# PCB-SSB-2x1.net
KiCad netlist of a schematic drawn in EAGLE
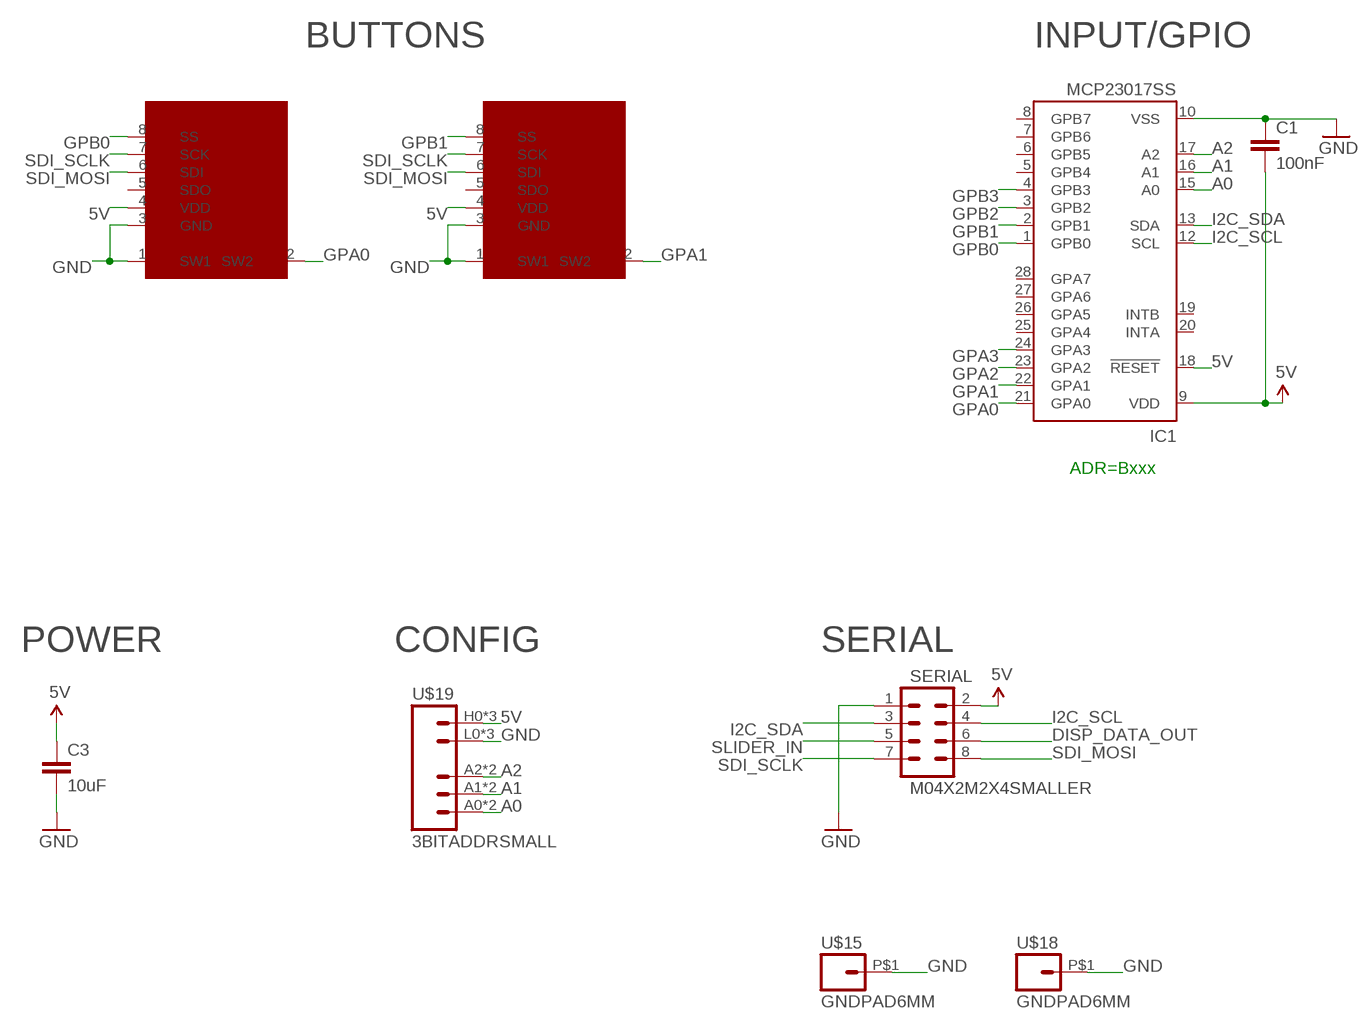
[diagram p0: schematic, sheet 1]

(export (version "E")
  (design (tool "Eeschema 10.0.6"))
  (components
    (comp (ref "C1")
      (value "100nF")
      (footprint "eagle-import:0603-CAP")
      (libsource (lib "eagle-import") (part "CAP0603-CAP"))
    )
    (comp (ref "C3")
      (value "10uF")
      (footprint "eagle-import:0805")
      (libsource (lib "eagle-import") (part "CAP0805"))
    )
    (comp (ref "IC1")
      (value "MCP23017SS")
      (footprint "eagle-import:SSOP28")
      (fields
        (field (name "MF") "MICROCHIP")
        (field (name "MPN") "MCP23017-E/SS")
        (field (name "MPN_1") "MCP23017-E/SS")
        (field (name "OC_FARNELL") "1467674")
        (field (name "OC_NEWARK") "31K2960")
      )
      (libsource (lib "eagle-import") (part "MCP23017SS"))
    )
    (comp (ref "SERIAL")
      (value "M04X2M2X4SMALLER")
      (footprint "eagle-import:M2X4SMALLER")
      (libsource (lib "eagle-import") (part "M04X2M2X4SMALLER"))
    )
    (comp (ref "SSW1")
      (value "SMART_SWITCHSMART_SWITCH_8PIN")
      (footprint "eagle-import:SMART_SWITCH")
      (libsource (lib "eagle-import") (part "SMART_SWITCHSMART_SWITCH_8PIN"))
    )
    (comp (ref "SSW2")
      (value "SMART_SWITCHSMART_SWITCH_8PIN")
      (footprint "eagle-import:SMART_SWITCH")
      (libsource (lib "eagle-import") (part "SMART_SWITCHSMART_SWITCH_8PIN"))
    )
    (comp (ref "U$15")
      (value "GNDPAD6MM")
      (footprint "eagle-import:3.2MMPAD6MM")
      (libsource (lib "eagle-import") (part "GNDPAD6MM"))
    )
    (comp (ref "U$18")
      (value "GNDPAD6MM")
      (footprint "eagle-import:3.2MMPAD6MM")
      (libsource (lib "eagle-import") (part "GNDPAD6MM"))
    )
    (comp (ref "U$19")
      (value "3BITADDRSMALL")
      (footprint "eagle-import:3BITADDR_SMALL")
      (libsource (lib "eagle-import") (part "3BITADDRSMALL"))
    )
  )
  (nets
    (net (code "1") (name "/A0") (class "Default")
      (node (ref "IC1") (pin "15") (pinfunction "A0_15") (pintype "input"))
      (node (ref "U$19") (pin "A0") (pinfunction "A0_A0") (pintype "passive"))
      (node (ref "U$19") (pin "AS0") (pinfunction "A0_AS0") (pintype "passive"))
    )
    (net (code "2") (name "/A1") (class "Default")
      (node (ref "IC1") (pin "16") (pinfunction "A1_16") (pintype "input"))
      (node (ref "U$19") (pin "A1") (pinfunction "A1_A1") (pintype "passive"))
      (node (ref "U$19") (pin "AS1") (pinfunction "A1_AS1") (pintype "passive"))
    )
    (net (code "3") (name "/A2") (class "Default")
      (node (ref "IC1") (pin "17") (pinfunction "A2_17") (pintype "input"))
      (node (ref "U$19") (pin "A2") (pinfunction "A2_A2") (pintype "passive"))
      (node (ref "U$19") (pin "AS2") (pinfunction "A2_AS2") (pintype "passive"))
    )
    (net (code "4") (name "/DISP_DATA_OUT") (class "Default")
      (node (ref "SERIAL") (pin "6") (pinfunction "6_6") (pintype "passive"))
    )
    (net (code "5") (name "/GPA0") (class "Default")
      (node (ref "IC1") (pin "21") (pinfunction "GPA0_21") (pintype "bidirectional"))
      (node (ref "SSW1") (pin "2") (pinfunction "SW2_2") (pintype "bidirectional"))
    )
    (net (code "6") (name "/GPA1") (class "Default")
      (node (ref "IC1") (pin "22") (pinfunction "GPA1_22") (pintype "bidirectional"))
      (node (ref "SSW2") (pin "2") (pinfunction "SW2_2") (pintype "bidirectional"))
    )
    (net (code "7") (name "/GPA2") (class "Default")
      (node (ref "IC1") (pin "23") (pinfunction "GPA2_23") (pintype "bidirectional"))
    )
    (net (code "8") (name "/GPA3") (class "Default")
      (node (ref "IC1") (pin "24") (pinfunction "GPA3_24") (pintype "bidirectional"))
    )
    (net (code "9") (name "/GPB0") (class "Default")
      (node (ref "IC1") (pin "1") (pinfunction "GPB0_1") (pintype "bidirectional"))
      (node (ref "SSW1") (pin "8") (pinfunction "SS_8") (pintype "bidirectional"))
    )
    (net (code "10") (name "/GPB1") (class "Default")
      (node (ref "IC1") (pin "2") (pinfunction "GPB1_2") (pintype "bidirectional"))
      (node (ref "SSW2") (pin "8") (pinfunction "SS_8") (pintype "bidirectional"))
    )
    (net (code "11") (name "/GPB2") (class "Default")
      (node (ref "IC1") (pin "3") (pinfunction "GPB2_3") (pintype "bidirectional"))
    )
    (net (code "12") (name "/GPB3") (class "Default")
      (node (ref "IC1") (pin "4") (pinfunction "GPB3_4") (pintype "bidirectional"))
    )
    (net (code "13") (name "/I2C_SCL") (class "Default")
      (node (ref "IC1") (pin "12") (pinfunction "SCL_12") (pintype "input"))
      (node (ref "SERIAL") (pin "4") (pinfunction "4_4") (pintype "passive"))
    )
    (net (code "14") (name "/I2C_SDA") (class "Default")
      (node (ref "IC1") (pin "13") (pinfunction "SDA_13") (pintype "bidirectional"))
      (node (ref "SERIAL") (pin "3") (pinfunction "3_3") (pintype "passive"))
    )
    (net (code "15") (name "/SDI_MOSI") (class "Default")
      (node (ref "SERIAL") (pin "8") (pinfunction "8_8") (pintype "passive"))
      (node (ref "SSW1") (pin "6") (pinfunction "SDI_6") (pintype "bidirectional"))
      (node (ref "SSW2") (pin "6") (pinfunction "SDI_6") (pintype "bidirectional"))
    )
    (net (code "16") (name "/SDI_SCLK") (class "Default")
      (node (ref "SERIAL") (pin "7") (pinfunction "7_7") (pintype "passive"))
      (node (ref "SSW1") (pin "7") (pinfunction "SCK_7") (pintype "bidirectional"))
      (node (ref "SSW2") (pin "7") (pinfunction "SCK_7") (pintype "bidirectional"))
    )
    (net (code "17") (name "/SLIDER_IN") (class "Default")
      (node (ref "SERIAL") (pin "5") (pinfunction "5_5") (pintype "passive"))
    )
    (net (code "18") (name "5V") (class "Default")
      (node (ref "C1") (pin "2") (pinfunction "2_2") (pintype "passive"))
      (node (ref "C3") (pin "1") (pinfunction "1_1") (pintype "passive"))
      (node (ref "IC1") (pin "18") (pinfunction "~{RESET}_18") (pintype "input"))
      (node (ref "IC1") (pin "9") (pinfunction "VDD_9") (pintype "power_in"))
      (node (ref "SERIAL") (pin "2") (pinfunction "2_2") (pintype "passive"))
      (node (ref "SSW1") (pin "4") (pinfunction "VDD_4") (pintype "bidirectional"))
      (node (ref "SSW2") (pin "4") (pinfunction "VDD_4") (pintype "bidirectional"))
      (node (ref "U$19") (pin "H0") (pinfunction "VCC_H0") (pintype "passive"))
      (node (ref "U$19") (pin "H1") (pinfunction "VCC_H1") (pintype "passive"))
      (node (ref "U$19") (pin "H2") (pinfunction "VCC_H2") (pintype "passive"))
    )
    (net (code "19") (name "GND") (class "Default")
      (node (ref "C1") (pin "1") (pinfunction "1_1") (pintype "passive"))
      (node (ref "C3") (pin "2") (pinfunction "2_2") (pintype "passive"))
      (node (ref "IC1") (pin "10") (pinfunction "VSS_10") (pintype "power_in"))
      (node (ref "SERIAL") (pin "1") (pinfunction "1_1") (pintype "passive"))
      (node (ref "SSW1") (pin "1") (pinfunction "SW1_1") (pintype "bidirectional"))
      (node (ref "SSW1") (pin "3") (pinfunction "GND_3") (pintype "bidirectional"))
      (node (ref "SSW2") (pin "1") (pinfunction "SW1_1") (pintype "bidirectional"))
      (node (ref "SSW2") (pin "3") (pinfunction "GND_3") (pintype "bidirectional"))
      (node (ref "U$15") (pin "P$1") (pinfunction "1_P$1") (pintype "passive"))
      (node (ref "U$18") (pin "P$1") (pinfunction "1_P$1") (pintype "passive"))
      (node (ref "U$19") (pin "L0") (pinfunction "GND_L0") (pintype "passive"))
      (node (ref "U$19") (pin "L1") (pinfunction "GND_L1") (pintype "passive"))
      (node (ref "U$19") (pin "L2") (pinfunction "GND_L2") (pintype "passive"))
    )
    (net (code "20") (name "unconnected-(IC1-GPA4-Pad25)") (class "Default")
      (node (ref "IC1") (pin "25") (pinfunction "GPA4_25") (pintype "bidirectional"))
    )
    (net (code "21") (name "unconnected-(IC1-GPA5-Pad26)") (class "Default")
      (node (ref "IC1") (pin "26") (pinfunction "GPA5_26") (pintype "bidirectional"))
    )
    (net (code "22") (name "unconnected-(IC1-GPA6-Pad27)") (class "Default")
      (node (ref "IC1") (pin "27") (pinfunction "GPA6_27") (pintype "bidirectional"))
    )
    (net (code "23") (name "unconnected-(IC1-GPA7-Pad28)") (class "Default")
      (node (ref "IC1") (pin "28") (pinfunction "GPA7_28") (pintype "bidirectional"))
    )
    (net (code "24") (name "unconnected-(IC1-GPB4-Pad5)") (class "Default")
      (node (ref "IC1") (pin "5") (pinfunction "GPB4_5") (pintype "bidirectional"))
    )
    (net (code "25") (name "unconnected-(IC1-GPB5-Pad6)") (class "Default")
      (node (ref "IC1") (pin "6") (pinfunction "GPB5_6") (pintype "bidirectional"))
    )
    (net (code "26") (name "unconnected-(IC1-GPB6-Pad7)") (class "Default")
      (node (ref "IC1") (pin "7") (pinfunction "GPB6_7") (pintype "bidirectional"))
    )
    (net (code "27") (name "unconnected-(IC1-GPB7-Pad8)") (class "Default")
      (node (ref "IC1") (pin "8") (pinfunction "GPB7_8") (pintype "bidirectional"))
    )
    (net (code "28") (name "unconnected-(IC1-INTA-Pad20)") (class "Default")
      (node (ref "IC1") (pin "20") (pinfunction "INTA_20") (pintype "output"))
    )
    (net (code "29") (name "unconnected-(IC1-INTB-Pad19)") (class "Default")
      (node (ref "IC1") (pin "19") (pinfunction "INTB_19") (pintype "output"))
    )
    (net (code "30") (name "unconnected-(SSW1-SDO-Pad5)") (class "Default")
      (node (ref "SSW1") (pin "5") (pinfunction "SDO_5") (pintype "bidirectional"))
    )
    (net (code "31") (name "unconnected-(SSW2-SDO-Pad5)") (class "Default")
      (node (ref "SSW2") (pin "5") (pinfunction "SDO_5") (pintype "bidirectional"))
    )
  )
)
